# button_brightness_esp32.net
KiCad netlist of a schematic drawn in Altium Designer
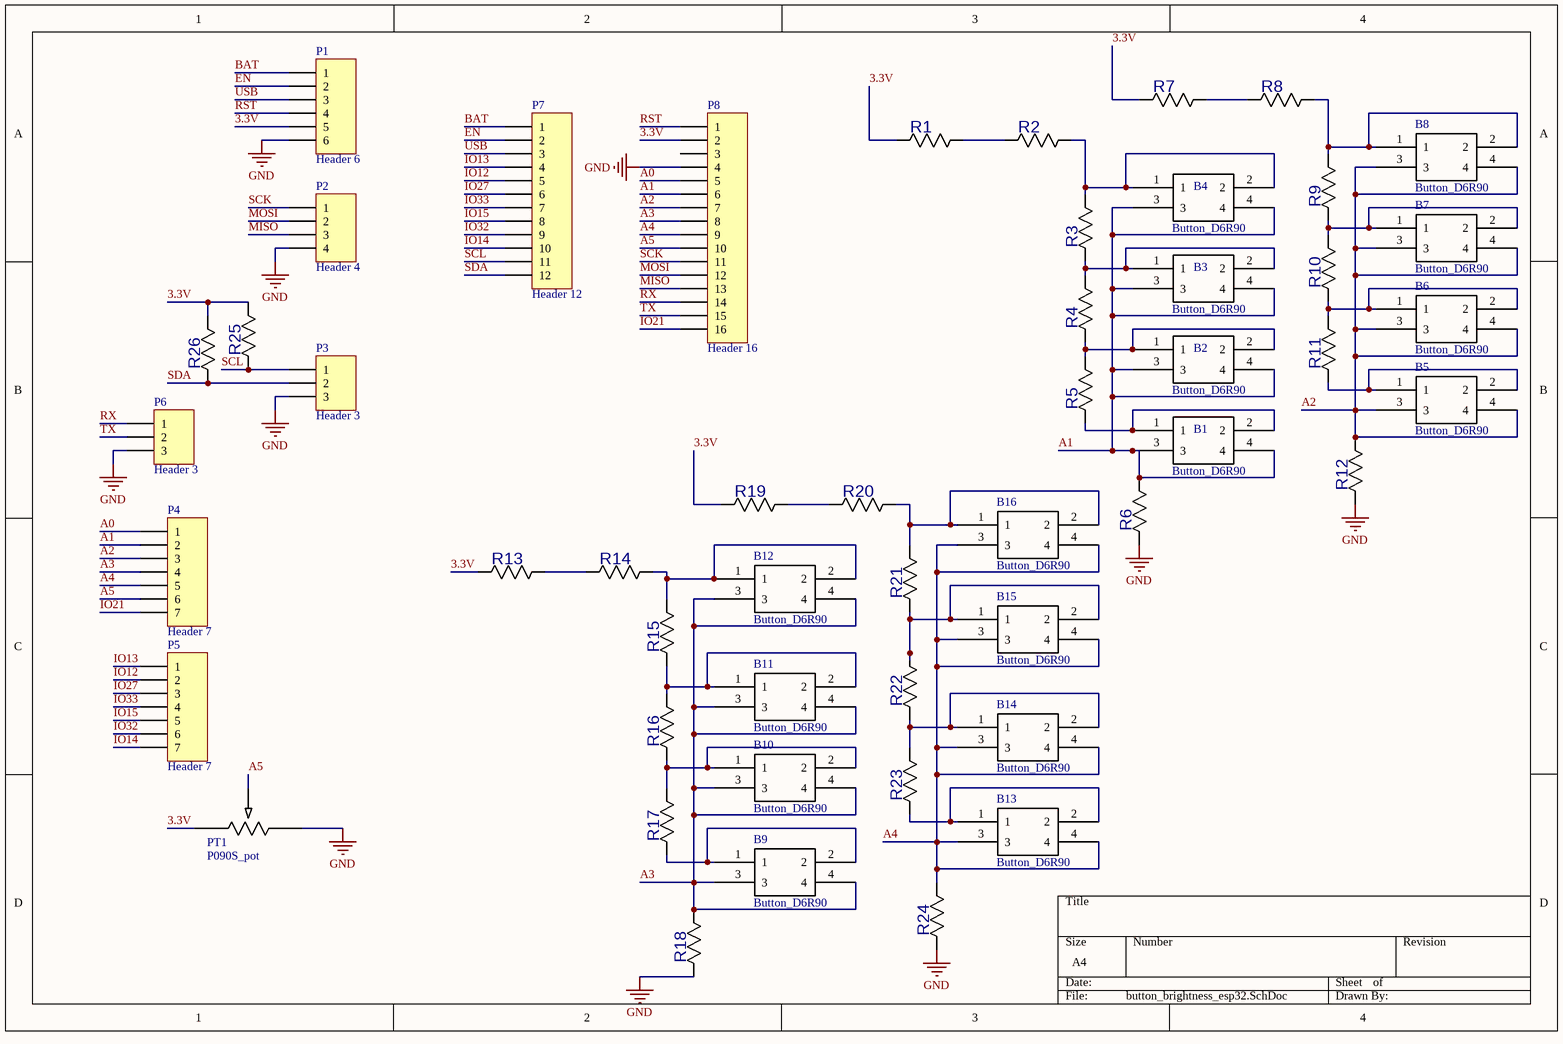
[diagram p0: button_brightness_esp32.SchDoc]

(export (version "E")
  (design (tool "Eeschema 10.0.6"))
  (components
    (comp (ref "B1")
      (value "Button_D6R90")
      (footprint "Button_D6R90")
      (libsource (lib "shematic_lib") (part "Button_D6R90"))
    )
    (comp (ref "B2")
      (value "Button_D6R90")
      (footprint "Button_D6R90")
      (libsource (lib "shematic_lib") (part "Button_D6R90"))
    )
    (comp (ref "B3")
      (value "Button_D6R90")
      (footprint "Button_D6R90")
      (libsource (lib "shematic_lib") (part "Button_D6R90"))
    )
    (comp (ref "B4")
      (value "Button_D6R90")
      (footprint "Button_D6R90")
      (libsource (lib "shematic_lib") (part "Button_D6R90"))
    )
    (comp (ref "B5")
      (value "Button_D6R90")
      (footprint "Button_D6R90")
      (libsource (lib "shematic_lib") (part "Button_D6R90"))
    )
    (comp (ref "B6")
      (value "Button_D6R90")
      (footprint "Button_D6R90")
      (libsource (lib "shematic_lib") (part "Button_D6R90"))
    )
    (comp (ref "B7")
      (value "Button_D6R90")
      (footprint "Button_D6R90")
      (libsource (lib "shematic_lib") (part "Button_D6R90"))
    )
    (comp (ref "B8")
      (value "Button_D6R90")
      (footprint "Button_D6R90")
      (libsource (lib "shematic_lib") (part "Button_D6R90"))
    )
    (comp (ref "B9")
      (value "Button_D6R90")
      (footprint "Button_D6R90")
      (libsource (lib "shematic_lib") (part "Button_D6R90"))
    )
    (comp (ref "B10")
      (value "Button_D6R90")
      (footprint "Button_D6R90")
      (libsource (lib "shematic_lib") (part "Button_D6R90"))
    )
    (comp (ref "B11")
      (value "Button_D6R90")
      (footprint "Button_D6R90")
      (libsource (lib "shematic_lib") (part "Button_D6R90"))
    )
    (comp (ref "B12")
      (value "Button_D6R90")
      (footprint "component_lib:Button_D6R90")
      (libsource (lib "shematic_lib") (part "Button_D6R90"))
    )
    (comp (ref "B13")
      (value "Button_D6R90")
      (footprint "Button_D6R90")
      (libsource (lib "shematic_lib") (part "Button_D6R90"))
    )
    (comp (ref "B14")
      (value "Button_D6R90")
      (footprint "Button_D6R90")
      (libsource (lib "shematic_lib") (part "Button_D6R90"))
    )
    (comp (ref "B15")
      (value "Button_D6R90")
      (footprint "Button_D6R90")
      (libsource (lib "shematic_lib") (part "Button_D6R90"))
    )
    (comp (ref "B16")
      (value "Button_D6R90")
      (footprint "Button_D6R90")
      (libsource (lib "shematic_lib") (part "Button_D6R90"))
    )
    (comp (ref "P1")
      (value "Header 6")
      (footprint "CONN_6")
      (description "Header, 6-Pin")
      (fields (field (name "PUBLISHER") "Altium Limited"))
      (libsource (lib "Miscellaneous Connectors") (part "Header 6"))
    )
    (comp (ref "P2")
      (value "Header 4")
      (footprint "CONN_4")
      (description "Header, 4-Pin")
      (fields (field (name "PUBLISHER") "Altium Limited"))
      (libsource (lib "Miscellaneous Connectors") (part "Header 4"))
    )
    (comp (ref "P3")
      (value "Header 3")
      (footprint "CONN_3")
      (description "Header, 3-Pin")
      (fields (field (name "PUBLISHER") "Altium Limited"))
      (libsource (lib "Miscellaneous Connectors") (part "Header 3"))
    )
    (comp (ref "P4")
      (value "Header 7")
      (footprint "CONN_7")
      (description "Header, 7-Pin")
      (fields (field (name "PUBLISHER") "Altium Limited"))
      (libsource (lib "Miscellaneous Connectors") (part "Header 7"))
    )
    (comp (ref "P5")
      (value "Header 7")
      (footprint "CONN_7")
      (description "Header, 7-Pin")
      (fields (field (name "PUBLISHER") "Altium Limited"))
      (libsource (lib "Miscellaneous Connectors") (part "Header 7"))
    )
    (comp (ref "P6")
      (value "Header 3")
      (footprint "CONN_3")
      (description "Header, 3-Pin")
      (fields (field (name "PUBLISHER") "Altium Limited"))
      (libsource (lib "Miscellaneous Connectors") (part "Header 3"))
    )
    (comp (ref "P7")
      (value "Header 12")
      (footprint "ESP32_feather_short_pins")
      (description "Header, 12-Pin")
      (fields (field (name "PUBLISHER") "Altium Limited"))
      (libsource (lib "Miscellaneous Connectors") (part "Header 12"))
    )
    (comp (ref "P8")
      (value "Header 16")
      (footprint "ESP32_feather_long_pins")
      (description "Header, 16-Pin")
      (fields (field (name "PUBLISHER") "Altium Limited"))
      (libsource (lib "Miscellaneous Connectors") (part "Header 16"))
    )
    (comp (ref "PT1")
      (value "P090S_pot")
      (footprint "POT_PTA2043")
      (libsource (lib "shematic_lib") (part "P090S_pot"))
    )
    (comp (ref "R1")
      (value "ERJ-6GEYJ471V")
      (footprint "component_lib:RES_0804_panasonic")
      (libsource (lib "shematic_lib") (part "ERJ-6GEYJ471V"))
    )
    (comp (ref "R2")
      (value "ERJ-6GEYJ471V")
      (footprint "component_lib:RES_0804_panasonic")
      (libsource (lib "shematic_lib") (part "ERJ-6GEYJ471V"))
    )
    (comp (ref "R3")
      (value "ERJ-6GEYJ471V")
      (footprint "component_lib:RES_0804_panasonic")
      (libsource (lib "shematic_lib") (part "ERJ-6GEYJ471V"))
    )
    (comp (ref "R4")
      (value "ERJ-6GEYJ471V")
      (footprint "component_lib:RES_0804_panasonic")
      (libsource (lib "shematic_lib") (part "ERJ-6GEYJ471V"))
    )
    (comp (ref "R5")
      (value "ERJ-6GEYJ471V")
      (footprint "component_lib:RES_0804_panasonic")
      (libsource (lib "shematic_lib") (part "ERJ-6GEYJ471V"))
    )
    (comp (ref "R6")
      (value "ERJ-6GEYJ471V")
      (footprint "component_lib:RES_0804_panasonic")
      (libsource (lib "shematic_lib") (part "ERJ-6GEYJ471V"))
    )
    (comp (ref "R7")
      (value "ERJ-6GEYJ471V")
      (footprint "component_lib:RES_0804_panasonic")
      (libsource (lib "shematic_lib") (part "ERJ-6GEYJ471V"))
    )
    (comp (ref "R8")
      (value "ERJ-6GEYJ471V")
      (footprint "component_lib:RES_0804_panasonic")
      (libsource (lib "shematic_lib") (part "ERJ-6GEYJ471V"))
    )
    (comp (ref "R9")
      (value "ERJ-6GEYJ471V")
      (footprint "component_lib:RES_0804_panasonic")
      (libsource (lib "shematic_lib") (part "ERJ-6GEYJ471V"))
    )
    (comp (ref "R10")
      (value "ERJ-6GEYJ471V")
      (footprint "component_lib:RES_0804_panasonic")
      (libsource (lib "shematic_lib") (part "ERJ-6GEYJ471V"))
    )
    (comp (ref "R11")
      (value "ERJ-6GEYJ471V")
      (footprint "component_lib:RES_0804_panasonic")
      (libsource (lib "shematic_lib") (part "ERJ-6GEYJ471V"))
    )
    (comp (ref "R12")
      (value "ERJ-6GEYJ471V")
      (footprint "component_lib:RES_0804_panasonic")
      (libsource (lib "shematic_lib") (part "ERJ-6GEYJ471V"))
    )
    (comp (ref "R13")
      (value "ERJ-6GEYJ471V")
      (footprint "component_lib:RES_0804_panasonic")
      (libsource (lib "shematic_lib") (part "ERJ-6GEYJ471V"))
    )
    (comp (ref "R14")
      (value "ERJ-6GEYJ471V")
      (footprint "component_lib:RES_0804_panasonic")
      (libsource (lib "shematic_lib") (part "ERJ-6GEYJ471V"))
    )
    (comp (ref "R15")
      (value "ERJ-6GEYJ471V")
      (footprint "component_lib:RES_0804_panasonic")
      (libsource (lib "shematic_lib") (part "ERJ-6GEYJ471V"))
    )
    (comp (ref "R16")
      (value "ERJ-6GEYJ471V")
      (footprint "component_lib:RES_0804_panasonic")
      (libsource (lib "shematic_lib") (part "ERJ-6GEYJ471V"))
    )
    (comp (ref "R17")
      (value "ERJ-6GEYJ471V")
      (footprint "component_lib:RES_0804_panasonic")
      (libsource (lib "shematic_lib") (part "ERJ-6GEYJ471V"))
    )
    (comp (ref "R18")
      (value "ERJ-6GEYJ471V")
      (footprint "component_lib:RES_0804_panasonic")
      (libsource (lib "shematic_lib") (part "ERJ-6GEYJ471V"))
    )
    (comp (ref "R19")
      (value "ERJ-6GEYJ471V")
      (footprint "component_lib:RES_0804_panasonic")
      (libsource (lib "shematic_lib") (part "ERJ-6GEYJ471V"))
    )
    (comp (ref "R20")
      (value "ERJ-6GEYJ471V")
      (footprint "component_lib:RES_0804_panasonic")
      (libsource (lib "shematic_lib") (part "ERJ-6GEYJ471V"))
    )
    (comp (ref "R21")
      (value "ERJ-6GEYJ471V")
      (footprint "component_lib:RES_0804_panasonic")
      (libsource (lib "shematic_lib") (part "ERJ-6GEYJ471V"))
    )
    (comp (ref "R22")
      (value "ERJ-6GEYJ471V")
      (footprint "component_lib:RES_0804_panasonic")
      (libsource (lib "shematic_lib") (part "ERJ-6GEYJ471V"))
    )
    (comp (ref "R23")
      (value "ERJ-6GEYJ471V")
      (footprint "component_lib:RES_0804_panasonic")
      (libsource (lib "shematic_lib") (part "ERJ-6GEYJ471V"))
    )
    (comp (ref "R24")
      (value "ERJ-6GEYJ471V")
      (footprint "component_lib:RES_0804_panasonic")
      (libsource (lib "shematic_lib") (part "ERJ-6GEYJ471V"))
    )
    (comp (ref "R25")
      (value "ERJ-6GEYJ471V")
      (footprint "component_lib:RES_0804_panasonic")
      (libsource (lib "shematic_lib") (part "ERJ-6GEYJ471V"))
    )
    (comp (ref "R26")
      (value "ERJ-6GEYJ471V")
      (footprint "component_lib:RES_0804_panasonic")
      (libsource (lib "shematic_lib") (part "ERJ-6GEYJ471V"))
    )
  )
  (nets
    (net (code "1") (name "/3.3V") (class "Default")
      (node (ref "P1") (pin "5") (pinfunction "5_5") (pintype "passive"))
      (node (ref "P8") (pin "2") (pinfunction "2_2") (pintype "passive"))
      (node (ref "PT1") (pin "1") (pinfunction "1_1") (pintype "passive"))
      (node (ref "R1") (pin "2") (pinfunction "2_2") (pintype "passive"))
      (node (ref "R13") (pin "2") (pinfunction "2_2") (pintype "passive"))
      (node (ref "R19") (pin "2") (pinfunction "2_2") (pintype "passive"))
      (node (ref "R25") (pin "1") (pinfunction "1_1") (pintype "passive"))
      (node (ref "R26") (pin "1") (pinfunction "1_1") (pintype "passive"))
      (node (ref "R7") (pin "2") (pinfunction "2_2") (pintype "passive"))
    )
    (net (code "2") (name "/A0") (class "Default")
      (node (ref "P4") (pin "1") (pinfunction "1_1") (pintype "passive"))
      (node (ref "P8") (pin "5") (pinfunction "5_5") (pintype "passive"))
    )
    (net (code "3") (name "/A1") (class "Default")
      (node (ref "B1") (pin "3") (pinfunction "3_3") (pintype "passive"))
      (node (ref "B1") (pin "4") (pinfunction "4_4") (pintype "passive"))
      (node (ref "B2") (pin "3") (pinfunction "3_3") (pintype "passive"))
      (node (ref "B2") (pin "4") (pinfunction "4_4") (pintype "passive"))
      (node (ref "B3") (pin "3") (pinfunction "3_3") (pintype "passive"))
      (node (ref "B3") (pin "4") (pinfunction "4_4") (pintype "passive"))
      (node (ref "B4") (pin "3") (pinfunction "3_3") (pintype "passive"))
      (node (ref "B4") (pin "4") (pinfunction "4_4") (pintype "passive"))
      (node (ref "P4") (pin "2") (pinfunction "2_2") (pintype "passive"))
      (node (ref "P8") (pin "6") (pinfunction "6_6") (pintype "passive"))
      (node (ref "R6") (pin "1") (pinfunction "1_1") (pintype "passive"))
    )
    (net (code "4") (name "/A2") (class "Default")
      (node (ref "B5") (pin "3") (pinfunction "3_3") (pintype "passive"))
      (node (ref "B5") (pin "4") (pinfunction "4_4") (pintype "passive"))
      (node (ref "B6") (pin "3") (pinfunction "3_3") (pintype "passive"))
      (node (ref "B6") (pin "4") (pinfunction "4_4") (pintype "passive"))
      (node (ref "B7") (pin "3") (pinfunction "3_3") (pintype "passive"))
      (node (ref "B7") (pin "4") (pinfunction "4_4") (pintype "passive"))
      (node (ref "B8") (pin "3") (pinfunction "3_3") (pintype "passive"))
      (node (ref "B8") (pin "4") (pinfunction "4_4") (pintype "passive"))
      (node (ref "P4") (pin "3") (pinfunction "3_3") (pintype "passive"))
      (node (ref "P8") (pin "7") (pinfunction "7_7") (pintype "passive"))
      (node (ref "R12") (pin "1") (pinfunction "1_1") (pintype "passive"))
    )
    (net (code "5") (name "/A3") (class "Default")
      (node (ref "B10") (pin "3") (pinfunction "3_3") (pintype "passive"))
      (node (ref "B10") (pin "4") (pinfunction "4_4") (pintype "passive"))
      (node (ref "B11") (pin "3") (pinfunction "3_3") (pintype "passive"))
      (node (ref "B11") (pin "4") (pinfunction "4_4") (pintype "passive"))
      (node (ref "B12") (pin "3") (pinfunction "3_3") (pintype "passive"))
      (node (ref "B12") (pin "4") (pinfunction "4_4") (pintype "passive"))
      (node (ref "B9") (pin "3") (pinfunction "3_3") (pintype "passive"))
      (node (ref "B9") (pin "4") (pinfunction "4_4") (pintype "passive"))
      (node (ref "P4") (pin "4") (pinfunction "4_4") (pintype "passive"))
      (node (ref "P8") (pin "8") (pinfunction "8_8") (pintype "passive"))
      (node (ref "R18") (pin "1") (pinfunction "1_1") (pintype "passive"))
    )
    (net (code "6") (name "/A4") (class "Default")
      (node (ref "B13") (pin "3") (pinfunction "3_3") (pintype "passive"))
      (node (ref "B13") (pin "4") (pinfunction "4_4") (pintype "passive"))
      (node (ref "B14") (pin "3") (pinfunction "3_3") (pintype "passive"))
      (node (ref "B14") (pin "4") (pinfunction "4_4") (pintype "passive"))
      (node (ref "B15") (pin "3") (pinfunction "3_3") (pintype "passive"))
      (node (ref "B15") (pin "4") (pinfunction "4_4") (pintype "passive"))
      (node (ref "B16") (pin "3") (pinfunction "3_3") (pintype "passive"))
      (node (ref "B16") (pin "4") (pinfunction "4_4") (pintype "passive"))
      (node (ref "P4") (pin "5") (pinfunction "5_5") (pintype "passive"))
      (node (ref "P8") (pin "9") (pinfunction "9_9") (pintype "passive"))
      (node (ref "R24") (pin "1") (pinfunction "1_1") (pintype "passive"))
    )
    (net (code "7") (name "/A5") (class "Default")
      (node (ref "P4") (pin "6") (pinfunction "6_6") (pintype "passive"))
      (node (ref "P8") (pin "10") (pinfunction "10_10") (pintype "passive"))
      (node (ref "PT1") (pin "2") (pinfunction "2_2") (pintype "passive"))
    )
    (net (code "8") (name "/BAT") (class "Default")
      (node (ref "P1") (pin "1") (pinfunction "1_1") (pintype "passive"))
      (node (ref "P7") (pin "1") (pinfunction "1_1") (pintype "passive"))
    )
    (net (code "9") (name "/EN") (class "Default")
      (node (ref "P1") (pin "2") (pinfunction "2_2") (pintype "passive"))
      (node (ref "P7") (pin "2") (pinfunction "2_2") (pintype "passive"))
    )
    (net (code "10") (name "/IO12") (class "Default")
      (node (ref "P5") (pin "2") (pinfunction "2_2") (pintype "passive"))
      (node (ref "P7") (pin "5") (pinfunction "5_5") (pintype "passive"))
    )
    (net (code "11") (name "/IO13") (class "Default")
      (node (ref "P5") (pin "1") (pinfunction "1_1") (pintype "passive"))
      (node (ref "P7") (pin "4") (pinfunction "4_4") (pintype "passive"))
    )
    (net (code "12") (name "/IO14") (class "Default")
      (node (ref "P5") (pin "7") (pinfunction "7_7") (pintype "passive"))
      (node (ref "P7") (pin "10") (pinfunction "10_10") (pintype "passive"))
    )
    (net (code "13") (name "/IO15") (class "Default")
      (node (ref "P5") (pin "5") (pinfunction "5_5") (pintype "passive"))
      (node (ref "P7") (pin "8") (pinfunction "8_8") (pintype "passive"))
    )
    (net (code "14") (name "/IO21") (class "Default")
      (node (ref "P4") (pin "7") (pinfunction "7_7") (pintype "passive"))
      (node (ref "P8") (pin "16") (pinfunction "16_16") (pintype "passive"))
    )
    (net (code "15") (name "/IO27") (class "Default")
      (node (ref "P5") (pin "3") (pinfunction "3_3") (pintype "passive"))
      (node (ref "P7") (pin "6") (pinfunction "6_6") (pintype "passive"))
    )
    (net (code "16") (name "/IO32") (class "Default")
      (node (ref "P5") (pin "6") (pinfunction "6_6") (pintype "passive"))
      (node (ref "P7") (pin "9") (pinfunction "9_9") (pintype "passive"))
    )
    (net (code "17") (name "/IO33") (class "Default")
      (node (ref "P5") (pin "4") (pinfunction "4_4") (pintype "passive"))
      (node (ref "P7") (pin "7") (pinfunction "7_7") (pintype "passive"))
    )
    (net (code "18") (name "/MISO") (class "Default")
      (node (ref "P2") (pin "3") (pinfunction "3_3") (pintype "passive"))
      (node (ref "P8") (pin "13") (pinfunction "13_13") (pintype "passive"))
    )
    (net (code "19") (name "/MOSI") (class "Default")
      (node (ref "P2") (pin "2") (pinfunction "2_2") (pintype "passive"))
      (node (ref "P8") (pin "12") (pinfunction "12_12") (pintype "passive"))
    )
    (net (code "20") (name "/RST") (class "Default")
      (node (ref "P1") (pin "4") (pinfunction "4_4") (pintype "passive"))
      (node (ref "P8") (pin "1") (pinfunction "1_1") (pintype "passive"))
    )
    (net (code "21") (name "/RX") (class "Default")
      (node (ref "P6") (pin "1") (pinfunction "1_1") (pintype "passive"))
      (node (ref "P8") (pin "14") (pinfunction "14_14") (pintype "passive"))
    )
    (net (code "22") (name "/SCK") (class "Default")
      (node (ref "P2") (pin "1") (pinfunction "1_1") (pintype "passive"))
      (node (ref "P8") (pin "11") (pinfunction "11_11") (pintype "passive"))
    )
    (net (code "23") (name "/SCL") (class "Default")
      (node (ref "P3") (pin "1") (pinfunction "1_1") (pintype "passive"))
      (node (ref "P7") (pin "11") (pinfunction "11_11") (pintype "passive"))
      (node (ref "R25") (pin "2") (pinfunction "2_2") (pintype "passive"))
    )
    (net (code "24") (name "/SDA") (class "Default")
      (node (ref "P3") (pin "2") (pinfunction "2_2") (pintype "passive"))
      (node (ref "P7") (pin "12") (pinfunction "12_12") (pintype "passive"))
      (node (ref "R26") (pin "2") (pinfunction "2_2") (pintype "passive"))
    )
    (net (code "25") (name "/TX") (class "Default")
      (node (ref "P6") (pin "2") (pinfunction "2_2") (pintype "passive"))
      (node (ref "P8") (pin "15") (pinfunction "15_15") (pintype "passive"))
    )
    (net (code "26") (name "/USB") (class "Default")
      (node (ref "P1") (pin "3") (pinfunction "3_3") (pintype "passive"))
      (node (ref "P7") (pin "3") (pinfunction "3_3") (pintype "passive"))
    )
    (net (code "27") (name "GND") (class "Default")
      (node (ref "P1") (pin "6") (pinfunction "6_6") (pintype "passive"))
      (node (ref "P2") (pin "4") (pinfunction "4_4") (pintype "passive"))
      (node (ref "P3") (pin "3") (pinfunction "3_3") (pintype "passive"))
      (node (ref "P6") (pin "3") (pinfunction "3_3") (pintype "passive"))
      (node (ref "P8") (pin "4") (pinfunction "4_4") (pintype "passive"))
      (node (ref "PT1") (pin "3") (pinfunction "3_3") (pintype "passive"))
      (node (ref "R12") (pin "2") (pinfunction "2_2") (pintype "passive"))
      (node (ref "R18") (pin "2") (pinfunction "2_2") (pintype "passive"))
      (node (ref "R24") (pin "2") (pinfunction "2_2") (pintype "passive"))
      (node (ref "R6") (pin "2") (pinfunction "2_2") (pintype "passive"))
    )
    (net (code "28") (name "Net-(B1-Pad1)") (class "Default")
      (node (ref "B1") (pin "1") (pinfunction "1_1") (pintype "passive"))
      (node (ref "B1") (pin "2") (pinfunction "2_2") (pintype "passive"))
      (node (ref "R5") (pin "2") (pinfunction "2_2") (pintype "passive"))
    )
    (net (code "29") (name "Net-(B2-Pad1)") (class "Default")
      (node (ref "B2") (pin "1") (pinfunction "1_1") (pintype "passive"))
      (node (ref "B2") (pin "2") (pinfunction "2_2") (pintype "passive"))
      (node (ref "R4") (pin "2") (pinfunction "2_2") (pintype "passive"))
      (node (ref "R5") (pin "1") (pinfunction "1_1") (pintype "passive"))
    )
    (net (code "30") (name "Net-(B3-Pad1)") (class "Default")
      (node (ref "B3") (pin "1") (pinfunction "1_1") (pintype "passive"))
      (node (ref "B3") (pin "2") (pinfunction "2_2") (pintype "passive"))
      (node (ref "R3") (pin "2") (pinfunction "2_2") (pintype "passive"))
      (node (ref "R4") (pin "1") (pinfunction "1_1") (pintype "passive"))
    )
    (net (code "31") (name "Net-(B4-Pad1)") (class "Default")
      (node (ref "B4") (pin "1") (pinfunction "1_1") (pintype "passive"))
      (node (ref "B4") (pin "2") (pinfunction "2_2") (pintype "passive"))
      (node (ref "R2") (pin "1") (pinfunction "1_1") (pintype "passive"))
      (node (ref "R3") (pin "1") (pinfunction "1_1") (pintype "passive"))
    )
    (net (code "32") (name "Net-(B5-Pad1)") (class "Default")
      (node (ref "B5") (pin "1") (pinfunction "1_1") (pintype "passive"))
      (node (ref "B5") (pin "2") (pinfunction "2_2") (pintype "passive"))
      (node (ref "R11") (pin "2") (pinfunction "2_2") (pintype "passive"))
    )
    (net (code "33") (name "Net-(B6-Pad1)") (class "Default")
      (node (ref "B6") (pin "1") (pinfunction "1_1") (pintype "passive"))
      (node (ref "B6") (pin "2") (pinfunction "2_2") (pintype "passive"))
      (node (ref "R10") (pin "2") (pinfunction "2_2") (pintype "passive"))
      (node (ref "R11") (pin "1") (pinfunction "1_1") (pintype "passive"))
    )
    (net (code "34") (name "Net-(B7-Pad1)") (class "Default")
      (node (ref "B7") (pin "1") (pinfunction "1_1") (pintype "passive"))
      (node (ref "B7") (pin "2") (pinfunction "2_2") (pintype "passive"))
      (node (ref "R10") (pin "1") (pinfunction "1_1") (pintype "passive"))
      (node (ref "R9") (pin "2") (pinfunction "2_2") (pintype "passive"))
    )
    (net (code "35") (name "Net-(B8-Pad1)") (class "Default")
      (node (ref "B8") (pin "1") (pinfunction "1_1") (pintype "passive"))
      (node (ref "B8") (pin "2") (pinfunction "2_2") (pintype "passive"))
      (node (ref "R8") (pin "1") (pinfunction "1_1") (pintype "passive"))
      (node (ref "R9") (pin "1") (pinfunction "1_1") (pintype "passive"))
    )
    (net (code "36") (name "Net-(B9-Pad1)") (class "Default")
      (node (ref "B9") (pin "1") (pinfunction "1_1") (pintype "passive"))
      (node (ref "B9") (pin "2") (pinfunction "2_2") (pintype "passive"))
      (node (ref "R17") (pin "2") (pinfunction "2_2") (pintype "passive"))
    )
    (net (code "37") (name "Net-(B10-Pad1)") (class "Default")
      (node (ref "B10") (pin "1") (pinfunction "1_1") (pintype "passive"))
      (node (ref "B10") (pin "2") (pinfunction "2_2") (pintype "passive"))
      (node (ref "R16") (pin "2") (pinfunction "2_2") (pintype "passive"))
      (node (ref "R17") (pin "1") (pinfunction "1_1") (pintype "passive"))
    )
    (net (code "38") (name "Net-(B11-Pad1)") (class "Default")
      (node (ref "B11") (pin "1") (pinfunction "1_1") (pintype "passive"))
      (node (ref "B11") (pin "2") (pinfunction "2_2") (pintype "passive"))
      (node (ref "R15") (pin "2") (pinfunction "2_2") (pintype "passive"))
      (node (ref "R16") (pin "1") (pinfunction "1_1") (pintype "passive"))
    )
    (net (code "39") (name "Net-(B12-Pad1)") (class "Default")
      (node (ref "B12") (pin "1") (pinfunction "1_1") (pintype "passive"))
      (node (ref "B12") (pin "2") (pinfunction "2_2") (pintype "passive"))
      (node (ref "R14") (pin "1") (pinfunction "1_1") (pintype "passive"))
      (node (ref "R15") (pin "1") (pinfunction "1_1") (pintype "passive"))
    )
    (net (code "40") (name "Net-(B13-Pad1)") (class "Default")
      (node (ref "B13") (pin "1") (pinfunction "1_1") (pintype "passive"))
      (node (ref "B13") (pin "2") (pinfunction "2_2") (pintype "passive"))
      (node (ref "R23") (pin "2") (pinfunction "2_2") (pintype "passive"))
    )
    (net (code "41") (name "Net-(B14-Pad1)") (class "Default")
      (node (ref "B14") (pin "1") (pinfunction "1_1") (pintype "passive"))
      (node (ref "B14") (pin "2") (pinfunction "2_2") (pintype "passive"))
      (node (ref "R22") (pin "2") (pinfunction "2_2") (pintype "passive"))
      (node (ref "R23") (pin "1") (pinfunction "1_1") (pintype "passive"))
    )
    (net (code "42") (name "Net-(B15-Pad1)") (class "Default")
      (node (ref "B15") (pin "1") (pinfunction "1_1") (pintype "passive"))
      (node (ref "B15") (pin "2") (pinfunction "2_2") (pintype "passive"))
      (node (ref "R21") (pin "2") (pinfunction "2_2") (pintype "passive"))
      (node (ref "R22") (pin "1") (pinfunction "1_1") (pintype "passive"))
    )
    (net (code "43") (name "Net-(B16-Pad1)") (class "Default")
      (node (ref "B16") (pin "1") (pinfunction "1_1") (pintype "passive"))
      (node (ref "B16") (pin "2") (pinfunction "2_2") (pintype "passive"))
      (node (ref "R20") (pin "1") (pinfunction "1_1") (pintype "passive"))
      (node (ref "R21") (pin "1") (pinfunction "1_1") (pintype "passive"))
    )
    (net (code "44") (name "Net-(R1-Pad1)") (class "Default")
      (node (ref "R1") (pin "1") (pinfunction "1_1") (pintype "passive"))
      (node (ref "R2") (pin "2") (pinfunction "2_2") (pintype "passive"))
    )
    (net (code "45") (name "Net-(R7-Pad1)") (class "Default")
      (node (ref "R7") (pin "1") (pinfunction "1_1") (pintype "passive"))
      (node (ref "R8") (pin "2") (pinfunction "2_2") (pintype "passive"))
    )
    (net (code "46") (name "Net-(R13-Pad1)") (class "Default")
      (node (ref "R13") (pin "1") (pinfunction "1_1") (pintype "passive"))
      (node (ref "R14") (pin "2") (pinfunction "2_2") (pintype "passive"))
    )
    (net (code "47") (name "Net-(R19-Pad1)") (class "Default")
      (node (ref "R19") (pin "1") (pinfunction "1_1") (pintype "passive"))
      (node (ref "R20") (pin "2") (pinfunction "2_2") (pintype "passive"))
    )
    (net (code "48") (name "unconnected-(P8-Pad3)") (class "Default")
      (node (ref "P8") (pin "3") (pinfunction "3_3") (pintype "passive"))
    )
  )
)
